# Bramble.net
KiCad netlist of a schematic drawn in EAGLE
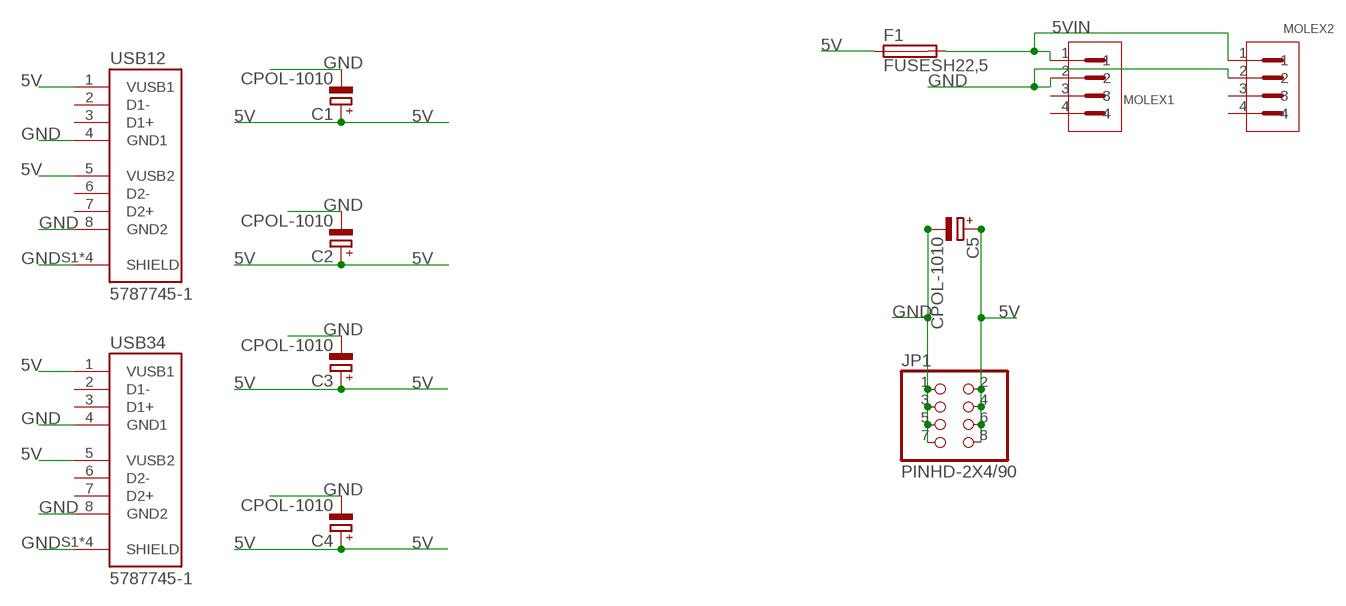
[diagram p0: schematic, sheet 1]

(export (version "E")
  (design (tool "Eeschema 10.0.6"))
  (components
    (comp (ref "C1")
      (value "CPOL-1010")
      (footprint "eagle-import:153CLV-1010")
      (libsource (lib "eagle-import") (part "CPOL-1010"))
    )
    (comp (ref "C2")
      (value "CPOL-1010")
      (footprint "eagle-import:153CLV-1010")
      (libsource (lib "eagle-import") (part "CPOL-1010"))
    )
    (comp (ref "C3")
      (value "CPOL-1010")
      (footprint "eagle-import:153CLV-1010")
      (libsource (lib "eagle-import") (part "CPOL-1010"))
    )
    (comp (ref "C4")
      (value "CPOL-1010")
      (footprint "eagle-import:153CLV-1010")
      (libsource (lib "eagle-import") (part "CPOL-1010"))
    )
    (comp (ref "C5")
      (value "CPOL-1010")
      (footprint "eagle-import:153CLV-1010")
      (libsource (lib "eagle-import") (part "CPOL-1010"))
    )
    (comp (ref "F1")
      (value "FUSESH22,5")
      (footprint "eagle-import:SH22,5")
      (libsource (lib "eagle-import") (part "FUSESH22,5"))
    )
    (comp (ref "JP1")
      (value "PINHD-2X4/90")
      (footprint "eagle-import:2X04_90")
      (libsource (lib "eagle-import") (part "PINHD-2X4/90"))
    )
    (comp (ref "MOLEX1")
      (value "15244441")
      (footprint "eagle-import:MOLEX_15244441")
      (fields (field (name "MF") "Molex") (field (name "MP") "15-24-4441"))
      (libsource (lib "eagle-import") (part "15244441"))
    )
    (comp (ref "MOLEX2")
      (value "15244441")
      (footprint "eagle-import:MOLEX_15244441")
      (fields (field (name "MF") "Molex") (field (name "MP") "15-24-4441"))
      (libsource (lib "eagle-import") (part "15244441"))
    )
    (comp (ref "USB12")
      (value "5787745-1")
      (footprint "eagle-import:TE_5787745-1")
      (fields (field (name "MF") "TE Connectivity"))
      (libsource (lib "eagle-import") (part "5787745-1"))
    )
    (comp (ref "USB34")
      (value "5787745-1")
      (footprint "eagle-import:TE_5787745-1")
      (fields (field (name "MF") "TE Connectivity"))
      (libsource (lib "eagle-import") (part "5787745-1"))
    )
  )
  (nets
    (net (code "1") (name "/5V") (class "Default")
      (node (ref "C1") (pin "+") (pinfunction "+_+") (pintype "passive"))
      (node (ref "C2") (pin "+") (pinfunction "+_+") (pintype "passive"))
      (node (ref "C3") (pin "+") (pinfunction "+_+") (pintype "passive"))
      (node (ref "C4") (pin "+") (pinfunction "+_+") (pintype "passive"))
      (node (ref "C5") (pin "+") (pinfunction "+_+") (pintype "passive"))
      (node (ref "F1") (pin "1") (pinfunction "1_1") (pintype "passive"))
      (node (ref "JP1") (pin "2") (pinfunction "2_2") (pintype "passive"))
      (node (ref "JP1") (pin "4") (pinfunction "4_4") (pintype "passive"))
      (node (ref "JP1") (pin "6") (pinfunction "6_6") (pintype "passive"))
      (node (ref "JP1") (pin "8") (pinfunction "8_8") (pintype "passive"))
      (node (ref "USB12") (pin "1") (pinfunction "VUSB1_1") (pintype "passive"))
      (node (ref "USB12") (pin "5") (pinfunction "VUSB2_5") (pintype "passive"))
      (node (ref "USB34") (pin "1") (pinfunction "VUSB1_1") (pintype "passive"))
      (node (ref "USB34") (pin "5") (pinfunction "VUSB2_5") (pintype "passive"))
    )
    (net (code "2") (name "/5VIN") (class "Default")
      (node (ref "F1") (pin "2") (pinfunction "2_2") (pintype "passive"))
      (node (ref "MOLEX1") (pin "1") (pinfunction "1_1") (pintype "passive"))
      (node (ref "MOLEX2") (pin "1") (pinfunction "1_1") (pintype "passive"))
    )
    (net (code "3") (name "/GND") (class "Default")
      (node (ref "C1") (pin "-") (pinfunction "-_-") (pintype "passive"))
      (node (ref "C2") (pin "-") (pinfunction "-_-") (pintype "passive"))
      (node (ref "C3") (pin "-") (pinfunction "-_-") (pintype "passive"))
      (node (ref "C4") (pin "-") (pinfunction "-_-") (pintype "passive"))
      (node (ref "C5") (pin "-") (pinfunction "-_-") (pintype "passive"))
      (node (ref "JP1") (pin "1") (pinfunction "1_1") (pintype "passive"))
      (node (ref "JP1") (pin "3") (pinfunction "3_3") (pintype "passive"))
      (node (ref "JP1") (pin "5") (pinfunction "5_5") (pintype "passive"))
      (node (ref "JP1") (pin "7") (pinfunction "7_7") (pintype "passive"))
      (node (ref "MOLEX1") (pin "2") (pinfunction "2_2") (pintype "passive"))
      (node (ref "MOLEX2") (pin "2") (pinfunction "2_2") (pintype "passive"))
      (node (ref "USB12") (pin "4") (pinfunction "GND1_4") (pintype "passive"))
      (node (ref "USB12") (pin "8") (pinfunction "GND2_8") (pintype "passive"))
      (node (ref "USB12") (pin "S1") (pinfunction "SHIELD_S1") (pintype "passive"))
      (node (ref "USB12") (pin "S2") (pinfunction "SHIELD_S2") (pintype "passive"))
      (node (ref "USB12") (pin "S3") (pinfunction "SHIELD_S3") (pintype "passive"))
      (node (ref "USB12") (pin "S4") (pinfunction "SHIELD_S4") (pintype "passive"))
      (node (ref "USB34") (pin "4") (pinfunction "GND1_4") (pintype "passive"))
      (node (ref "USB34") (pin "8") (pinfunction "GND2_8") (pintype "passive"))
      (node (ref "USB34") (pin "S1") (pinfunction "SHIELD_S1") (pintype "passive"))
      (node (ref "USB34") (pin "S2") (pinfunction "SHIELD_S2") (pintype "passive"))
      (node (ref "USB34") (pin "S3") (pinfunction "SHIELD_S3") (pintype "passive"))
      (node (ref "USB34") (pin "S4") (pinfunction "SHIELD_S4") (pintype "passive"))
    )
    (net (code "4") (name "unconnected-(MOLEX1-Pad3)") (class "Default")
      (node (ref "MOLEX1") (pin "3") (pinfunction "3_3") (pintype "passive"))
    )
    (net (code "5") (name "unconnected-(MOLEX1-Pad4)") (class "Default")
      (node (ref "MOLEX1") (pin "4") (pinfunction "4_4") (pintype "passive"))
    )
    (net (code "6") (name "unconnected-(MOLEX2-Pad3)") (class "Default")
      (node (ref "MOLEX2") (pin "3") (pinfunction "3_3") (pintype "passive"))
    )
    (net (code "7") (name "unconnected-(MOLEX2-Pad4)") (class "Default")
      (node (ref "MOLEX2") (pin "4") (pinfunction "4_4") (pintype "passive"))
    )
    (net (code "8") (name "unconnected-(USB12-D1+-Pad3)") (class "Default")
      (node (ref "USB12") (pin "3") (pinfunction "D1+_3") (pintype "passive"))
    )
    (net (code "9") (name "unconnected-(USB12-D1--Pad2)") (class "Default")
      (node (ref "USB12") (pin "2") (pinfunction "D1-_2") (pintype "passive"))
    )
    (net (code "10") (name "unconnected-(USB12-D2+-Pad7)") (class "Default")
      (node (ref "USB12") (pin "7") (pinfunction "D2+_7") (pintype "passive"))
    )
    (net (code "11") (name "unconnected-(USB12-D2--Pad6)") (class "Default")
      (node (ref "USB12") (pin "6") (pinfunction "D2-_6") (pintype "passive"))
    )
    (net (code "12") (name "unconnected-(USB34-D1+-Pad3)") (class "Default")
      (node (ref "USB34") (pin "3") (pinfunction "D1+_3") (pintype "passive"))
    )
    (net (code "13") (name "unconnected-(USB34-D1--Pad2)") (class "Default")
      (node (ref "USB34") (pin "2") (pinfunction "D1-_2") (pintype "passive"))
    )
    (net (code "14") (name "unconnected-(USB34-D2+-Pad7)") (class "Default")
      (node (ref "USB34") (pin "7") (pinfunction "D2+_7") (pintype "passive"))
    )
    (net (code "15") (name "unconnected-(USB34-D2--Pad6)") (class "Default")
      (node (ref "USB34") (pin "6") (pinfunction "D2-_6") (pintype "passive"))
    )
  )
)
